# LORA.net
KiCad netlist of a schematic drawn in Altium Designer
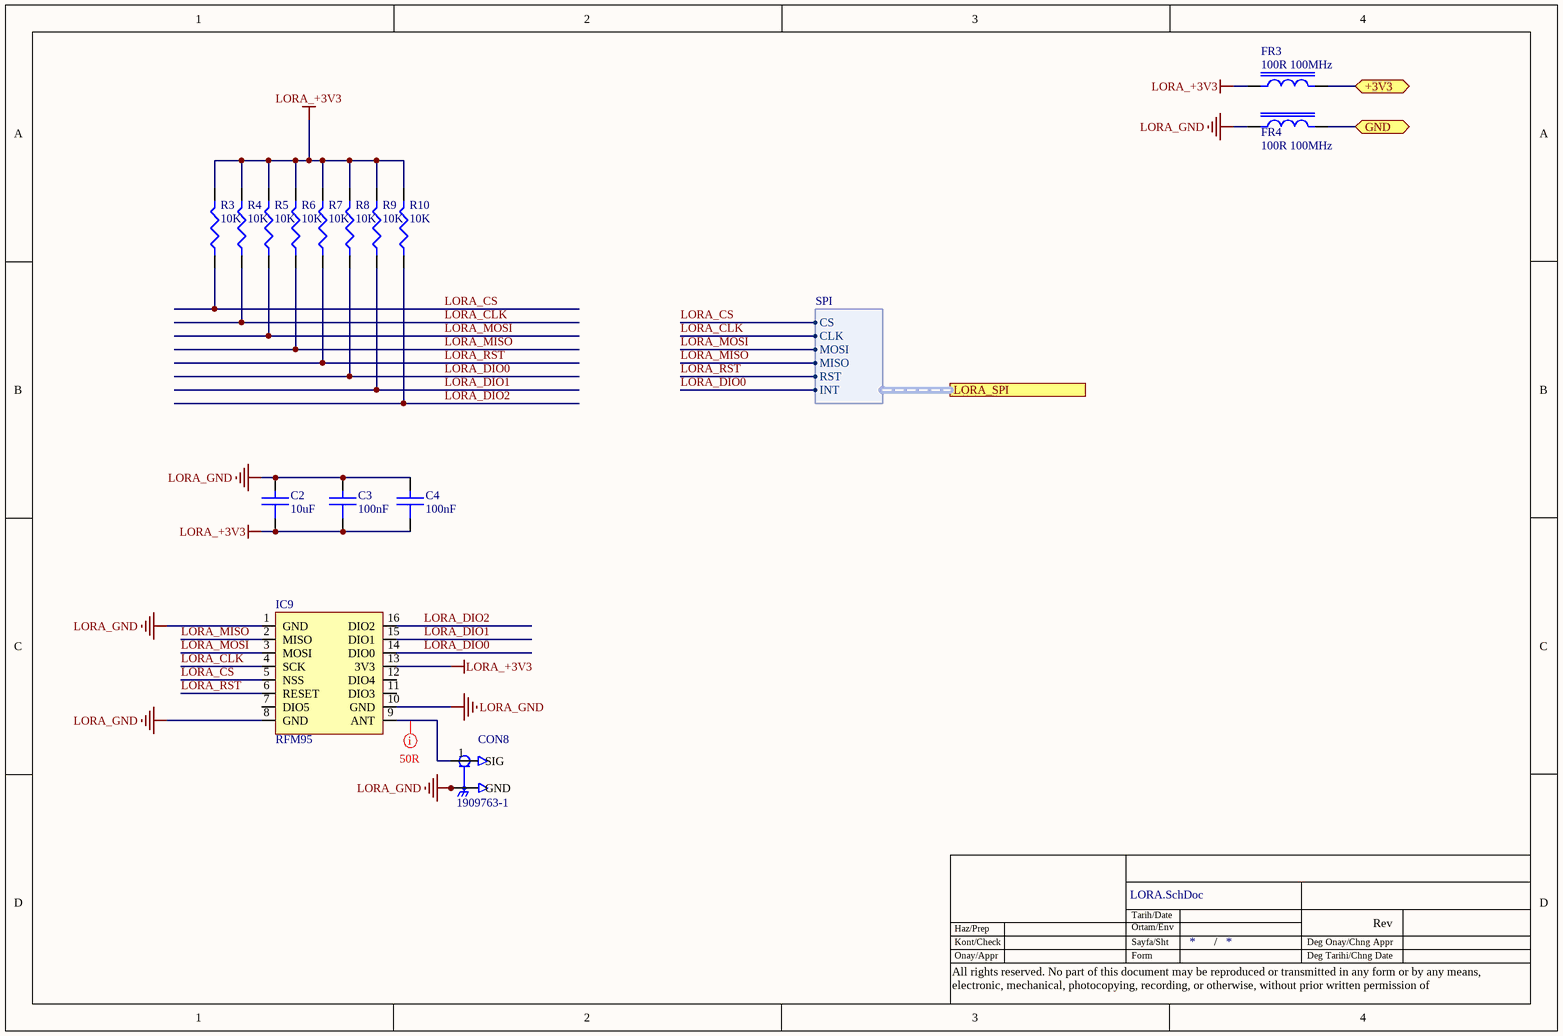
[diagram p0: LORA.SchDoc]

(export (version "E")
  (design (tool "Eeschema 10.0.6"))
  (components
    (comp (ref "C2")
      (value "10uF")
      (footprint "C0603")
      (description "10uF 10V X5R 20% SMD 0603 85C Paper T/R")
      (fields
        (field (name "MANUFACTURER") "Yageo")
        (field (name "MANUFACTURER PART NUMBER") "CC0603MRX5R6BB106")
      )
      (libsource (lib "McmLibrary") (part "CC0603MRX5R6BB106"))
    )
    (comp (ref "C3")
      (value "100nF")
      (footprint "C0603")
      (description "100nF, 25V, X7R, 10%, 0603")
      (fields
        (field (name "MANUFACTURER") "Yageo")
        (field (name "MANUFACTURER PART NUMBER") "CC0603KRX7R8BB104")
      )
      (libsource (lib "McmLibrary") (part "CC0603KRX7R8BB104"))
    )
    (comp (ref "C4")
      (value "100nF")
      (footprint "C0603")
      (description "100nF, 25V, X7R, 10%, 0603")
      (fields
        (field (name "MANUFACTURER") "Yageo")
        (field (name "MANUFACTURER PART NUMBER") "CC0603KRX7R8BB104")
      )
      (libsource (lib "McmLibrary") (part "CC0603KRX7R8BB104"))
    )
    (comp (ref "CON8")
      (value "1909763-1")
      (footprint "TE_1909763-1")
      (description "CONN UMCC JACK STR 50OHM SMD")
      (fields (field (name "MANUFACTURER") "TE Connectivity AMP"))
      (libsource (lib "McmLibrary") (part "1909763-1"))
    )
    (comp (ref "FR3")
      (value "100R 100MHz")
      (footprint "FR_0603")
      (description "100Ohm 100MHz 500mA 0603 SMD")
      (fields
        (field (name "MANUFACTURER") "Wurth Electronics")
        (field (name "MANUFACTURER PART NUMBER") "742792620")
      )
      (libsource (lib "McmLibrary") (part "742792620"))
    )
    (comp (ref "FR4")
      (value "100R 100MHz")
      (footprint "FR_0603")
      (description "100Ohm 100MHz 500mA 0603 SMD")
      (fields
        (field (name "MANUFACTURER") "Wurth Electronics")
        (field (name "MANUFACTURER PART NUMBER") "742792620")
      )
      (libsource (lib "McmLibrary") (part "742792620"))
    )
    (comp (ref "IC9")
      (value "RFM95")
      (footprint "RFM95")
      (description "RFM95 ULTRA-LONG RANGE TRANSCEIV")
      (fields
        (field (name "MANUFACTURER") "Seeed Studio")
        (field (name "MANUFACTURER PART NUMBER") "109990166")
      )
      (libsource (lib "Module") (part "RFM95"))
    )
    (comp (ref "R3")
      (value "10K")
      (footprint "R0603")
      (description "10K OHM 1% 1/10W 0603")
      (fields
        (field (name "MANUFACTURER") "Yageo")
        (field (name "MANUFACTURER PART NUMBER") "RT0603FRE0710KL")
      )
      (libsource (lib "McmLibrary") (part "RT0603FRE0710KL"))
    )
    (comp (ref "R4")
      (value "10K")
      (footprint "R0603")
      (description "10K OHM 1% 1/10W 0603")
      (fields
        (field (name "MANUFACTURER") "Yageo")
        (field (name "MANUFACTURER PART NUMBER") "RT0603FRE0710KL")
      )
      (libsource (lib "McmLibrary") (part "RT0603FRE0710KL"))
    )
    (comp (ref "R5")
      (value "10K")
      (footprint "R0603")
      (description "10K OHM 1% 1/10W 0603")
      (fields
        (field (name "MANUFACTURER") "Yageo")
        (field (name "MANUFACTURER PART NUMBER") "RT0603FRE0710KL")
      )
      (libsource (lib "McmLibrary") (part "RT0603FRE0710KL"))
    )
    (comp (ref "R6")
      (value "10K")
      (footprint "R0603")
      (description "10K OHM 1% 1/10W 0603")
      (fields
        (field (name "MANUFACTURER") "Yageo")
        (field (name "MANUFACTURER PART NUMBER") "RT0603FRE0710KL")
      )
      (libsource (lib "McmLibrary") (part "RT0603FRE0710KL"))
    )
    (comp (ref "R7")
      (value "10K")
      (footprint "R0603")
      (description "10K OHM 1% 1/10W 0603")
      (fields
        (field (name "MANUFACTURER") "Yageo")
        (field (name "MANUFACTURER PART NUMBER") "RT0603FRE0710KL")
      )
      (libsource (lib "McmLibrary") (part "RT0603FRE0710KL"))
    )
    (comp (ref "R8")
      (value "10K")
      (footprint "R0603")
      (description "10K OHM 1% 1/10W 0603")
      (fields
        (field (name "MANUFACTURER") "Yageo")
        (field (name "MANUFACTURER PART NUMBER") "RT0603FRE0710KL")
      )
      (libsource (lib "McmLibrary") (part "RT0603FRE0710KL"))
    )
    (comp (ref "R9")
      (value "10K")
      (footprint "R0603")
      (description "10K OHM 1% 1/10W 0603")
      (fields
        (field (name "MANUFACTURER") "Yageo")
        (field (name "MANUFACTURER PART NUMBER") "RT0603FRE0710KL")
      )
      (libsource (lib "McmLibrary") (part "RT0603FRE0710KL"))
    )
    (comp (ref "R10")
      (value "10K")
      (footprint "R0603")
      (description "10K OHM 1% 1/10W 0603")
      (fields
        (field (name "MANUFACTURER") "Yageo")
        (field (name "MANUFACTURER PART NUMBER") "RT0603FRE0710KL")
      )
      (libsource (lib "McmLibrary") (part "RT0603FRE0710KL"))
    )
  )
  (nets
    (net (code "2") (name "/+3V3") (class "Default")
      (node (ref "FR3") (pin "2") (pinfunction "2_2") (pintype "passive"))
    )
    (net (code "3") (name "/GND") (class "Default")
      (node (ref "FR4") (pin "2") (pinfunction "2_2") (pintype "passive"))
    )
    (net (code "4") (name "/LORA_CLK") (class "Default")
      (node (ref "IC9") (pin "4") (pinfunction "SCK_4") (pintype "passive"))
      (node (ref "R4") (pin "1") (pinfunction "1_1") (pintype "passive"))
    )
    (net (code "5") (name "/LORA_CS") (class "Default")
      (node (ref "IC9") (pin "5") (pinfunction "NSS_5") (pintype "passive"))
      (node (ref "R3") (pin "1") (pinfunction "1_1") (pintype "passive"))
    )
    (net (code "6") (name "/LORA_DIO0") (class "Default")
      (node (ref "IC9") (pin "14") (pinfunction "DIO0_14") (pintype "passive"))
      (node (ref "R8") (pin "1") (pinfunction "1_1") (pintype "passive"))
    )
    (net (code "7") (name "/LORA_DIO1") (class "Default")
      (node (ref "IC9") (pin "15") (pinfunction "DIO1_15") (pintype "passive"))
      (node (ref "R9") (pin "1") (pinfunction "1_1") (pintype "passive"))
    )
    (net (code "8") (name "/LORA_DIO2") (class "Default")
      (node (ref "IC9") (pin "16") (pinfunction "DIO2_16") (pintype "passive"))
      (node (ref "R10") (pin "1") (pinfunction "1_1") (pintype "passive"))
    )
    (net (code "9") (name "/LORA_MISO") (class "Default")
      (node (ref "IC9") (pin "2") (pinfunction "MISO_2") (pintype "passive"))
      (node (ref "R6") (pin "1") (pinfunction "1_1") (pintype "passive"))
    )
    (net (code "10") (name "/LORA_MOSI") (class "Default")
      (node (ref "IC9") (pin "3") (pinfunction "MOSI_3") (pintype "passive"))
      (node (ref "R5") (pin "1") (pinfunction "1_1") (pintype "passive"))
    )
    (net (code "11") (name "/LORA_RST") (class "Default")
      (node (ref "IC9") (pin "6") (pinfunction "RESET_6") (pintype "passive"))
      (node (ref "R7") (pin "1") (pinfunction "1_1") (pintype "passive"))
    )
    (net (code "13") (name "LORA_+3V3") (class "Default")
      (node (ref "C2") (pin "2") (pintype "passive"))
      (node (ref "C3") (pin "2") (pintype "passive"))
      (node (ref "C4") (pin "2") (pintype "passive"))
      (node (ref "FR3") (pin "1") (pinfunction "1_1") (pintype "passive"))
      (node (ref "IC9") (pin "13") (pinfunction "3V3_13") (pintype "passive"))
      (node (ref "R10") (pin "2") (pinfunction "2_2") (pintype "passive"))
      (node (ref "R3") (pin "2") (pinfunction "2_2") (pintype "passive"))
      (node (ref "R4") (pin "2") (pinfunction "2_2") (pintype "passive"))
      (node (ref "R5") (pin "2") (pinfunction "2_2") (pintype "passive"))
      (node (ref "R6") (pin "2") (pinfunction "2_2") (pintype "passive"))
      (node (ref "R7") (pin "2") (pinfunction "2_2") (pintype "passive"))
      (node (ref "R8") (pin "2") (pinfunction "2_2") (pintype "passive"))
      (node (ref "R9") (pin "2") (pinfunction "2_2") (pintype "passive"))
    )
    (net (code "14") (name "LORA_GND") (class "Default")
      (node (ref "C2") (pin "1") (pintype "passive"))
      (node (ref "C3") (pin "1") (pintype "passive"))
      (node (ref "C4") (pin "1") (pintype "passive"))
      (node (ref "CON8") (pin "2") (pinfunction "GND_2") (pintype "passive"))
      (node (ref "CON8") (pin "3") (pinfunction "GND_3") (pintype "passive"))
      (node (ref "FR4") (pin "1") (pinfunction "1_1") (pintype "passive"))
      (node (ref "IC9") (pin "1") (pinfunction "GND_1") (pintype "passive"))
      (node (ref "IC9") (pin "10") (pinfunction "GND_10") (pintype "passive"))
      (node (ref "IC9") (pin "8") (pinfunction "GND_8") (pintype "passive"))
    )
    (net (code "15") (name "Net-(CON8-SIG)") (class "Default")
      (node (ref "CON8") (pin "1") (pinfunction "SIG_1") (pintype "passive"))
      (node (ref "IC9") (pin "9") (pinfunction "ANT_9") (pintype "passive"))
    )
    (net (code "16") (name "unconnected-(IC9-DIO3-Pad11)") (class "Default")
      (node (ref "IC9") (pin "11") (pinfunction "DIO3_11") (pintype "passive"))
    )
    (net (code "17") (name "unconnected-(IC9-DIO4-Pad12)") (class "Default")
      (node (ref "IC9") (pin "12") (pinfunction "DIO4_12") (pintype "passive"))
    )
    (net (code "18") (name "unconnected-(IC9-DIO5-Pad7)") (class "Default")
      (node (ref "IC9") (pin "7") (pinfunction "DIO5_7") (pintype "passive"))
    )
  )
)
